# board.net
KiCad netlist of a schematic drawn in EAGLE
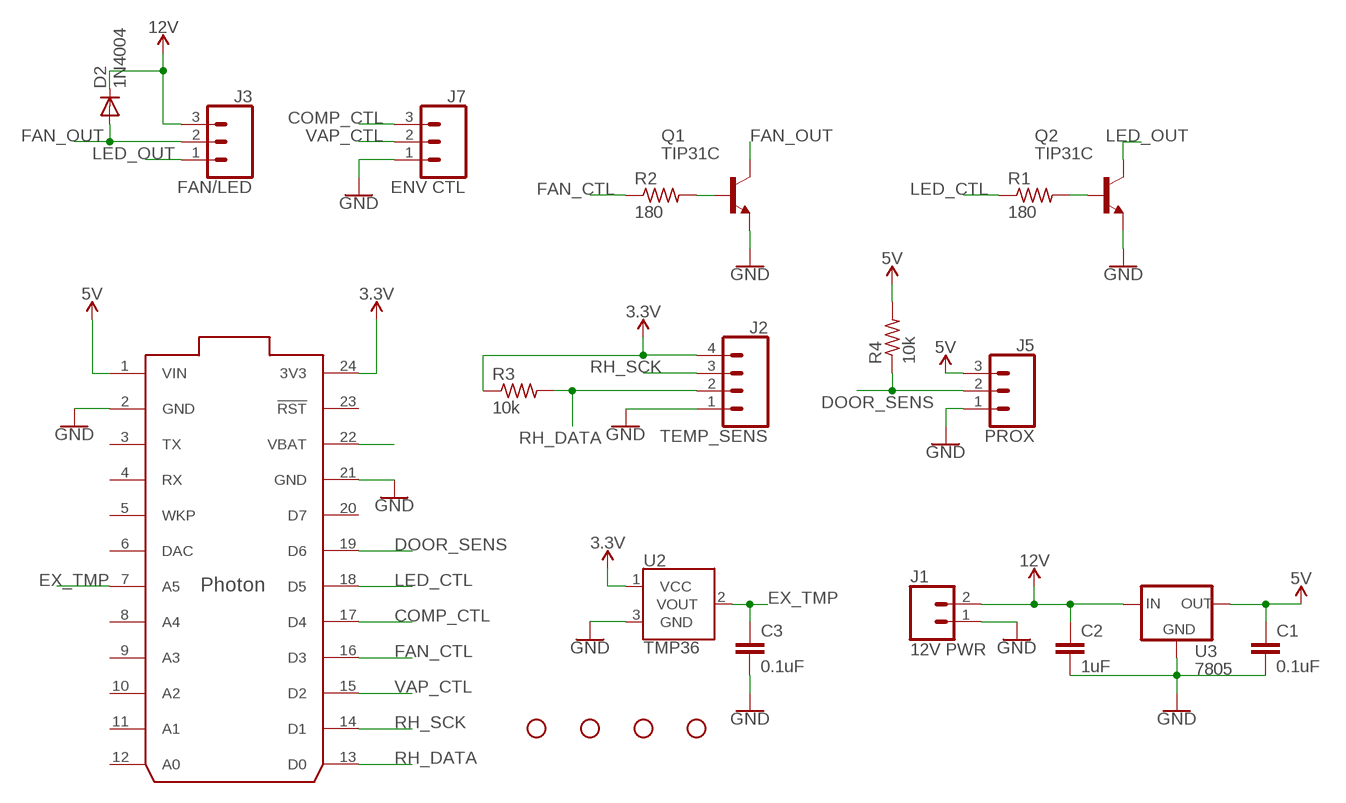
[diagram p0: schematic, sheet 1]

(export (version "E")
  (design (tool "Eeschema 10.0.6"))
  (components
    (comp (ref "C1")
      (value "0.1uF")
      (footprint "eagle-import:CAP-PTH-SMALL-KIT")
      (libsource (lib "eagle-import") (part "0.1UF-KIT-EZ-50V-20%"))
    )
    (comp (ref "C2")
      (value "1uF")
      (footprint "eagle-import:CAP-PTH-SMALL-KIT")
      (libsource (lib "eagle-import") (part "0.1UF-KIT-EZ-50V-20%"))
    )
    (comp (ref "C3")
      (value "0.1uF")
      (footprint "eagle-import:CAP-PTH-SMALL-KIT")
      (libsource (lib "eagle-import") (part "0.1UF-KIT-EZ-50V-20%"))
    )
    (comp (ref "D2")
      (value "1N4004")
      (footprint "eagle-import:DO41-10")
      (libsource (lib "eagle-import") (part "1N4004"))
    )
    (comp (ref "H1")
      (value "STAND-OFF")
      (footprint "eagle-import:STAND-OFF")
      (libsource (lib "eagle-import") (part "STAND-OFF"))
    )
    (comp (ref "H2")
      (value "STAND-OFF")
      (footprint "eagle-import:STAND-OFF")
      (libsource (lib "eagle-import") (part "STAND-OFF"))
    )
    (comp (ref "H3")
      (value "STAND-OFF")
      (footprint "eagle-import:STAND-OFF")
      (libsource (lib "eagle-import") (part "STAND-OFF"))
    )
    (comp (ref "H4")
      (value "STAND-OFF")
      (footprint "eagle-import:STAND-OFF")
      (libsource (lib "eagle-import") (part "STAND-OFF"))
    )
    (comp (ref "J1")
      (value "12V PWR")
      (footprint "eagle-import:SCREWTERMINAL-3.5MM-2")
      (libsource (lib "eagle-import") (part "CONN_023.5MM"))
    )
    (comp (ref "J2")
      (value "TEMP_SENS")
      (footprint "eagle-import:SCREWTERMINAL-3.5MM-4_LOCK")
      (libsource (lib "eagle-import") (part "CONN_04SCREW_LOCK"))
    )
    (comp (ref "J3")
      (value "FAN/LED")
      (footprint "eagle-import:SCREWTERMINAL-5MM-3")
      (libsource (lib "eagle-import") (part "CONN_03-SCREW-5MM"))
    )
    (comp (ref "J5")
      (value "PROX")
      (footprint "eagle-import:SCREWTERMINAL-5MM-3")
      (libsource (lib "eagle-import") (part "CONN_03-SCREW-5MM"))
    )
    (comp (ref "J7")
      (value "ENV CTL")
      (footprint "eagle-import:SCREWTERMINAL-5MM-3")
      (libsource (lib "eagle-import") (part "CONN_03-SCREW-5MM"))
    )
    (comp (ref "Q1")
      (value "TIP31C")
      (footprint "eagle-import:TO220")
      (libsource (lib "eagle-import") (part "TIP31C"))
    )
    (comp (ref "Q2")
      (value "TIP31C")
      (footprint "eagle-import:TO220")
      (libsource (lib "eagle-import") (part "TIP31C"))
    )
    (comp (ref "R1")
      (value "180")
      (footprint "eagle-import:0207_10")
      (libsource (lib "eagle-import") (part "R-US_0207/10"))
    )
    (comp (ref "R2")
      (value "180")
      (footprint "eagle-import:0207_10")
      (libsource (lib "eagle-import") (part "R-US_0207/10"))
    )
    (comp (ref "R3")
      (value "10k")
      (footprint "eagle-import:0207_10")
      (libsource (lib "eagle-import") (part "R-US_0207/10"))
    )
    (comp (ref "R4")
      (value "10k")
      (footprint "eagle-import:0207_10")
      (libsource (lib "eagle-import") (part "R-US_0207/10"))
    )
    (comp (ref "U$1")
      (value "PHOTON_SMD")
      (footprint "eagle-import:PHOTON_SMD")
      (libsource (lib "eagle-import") (part "PHOTON_SMD"))
    )
    (comp (ref "U2")
      (value "TMP36")
      (footprint "eagle-import:TO-92")
      (libsource (lib "eagle-import") (part "TMP36GT9"))
    )
    (comp (ref "U3")
      (value "7805")
      (footprint "eagle-import:TO-220-ALT")
      (libsource (lib "eagle-import") (part "V_REG_78XX-TO-220"))
    )
  )
  (nets
    (net (code "1") (name "/COMP_CTL") (class "Default")
      (node (ref "J7") (pin "3") (pinfunction "3_3") (pintype "passive"))
      (node (ref "U$1") (pin "17") (pinfunction "D4_17") (pintype "bidirectional"))
    )
    (net (code "2") (name "/DOOR_SENS") (class "Default")
      (node (ref "J5") (pin "2") (pinfunction "2_2") (pintype "passive"))
      (node (ref "R4") (pin "1") (pinfunction "1_1") (pintype "passive"))
      (node (ref "U$1") (pin "19") (pinfunction "D6_19") (pintype "bidirectional"))
    )
    (net (code "3") (name "/EX_TMP") (class "Default")
      (node (ref "C3") (pin "1") (pinfunction "1_1") (pintype "passive"))
      (node (ref "U$1") (pin "7") (pinfunction "A5_7") (pintype "bidirectional"))
      (node (ref "U2") (pin "2") (pinfunction "VOUT_2") (pintype "bidirectional"))
    )
    (net (code "4") (name "/FAN_CTL") (class "Default")
      (node (ref "R2") (pin "1") (pinfunction "1_1") (pintype "passive"))
      (node (ref "U$1") (pin "16") (pinfunction "D3_16") (pintype "bidirectional"))
    )
    (net (code "5") (name "/FAN_OUT") (class "Default")
      (node (ref "D2") (pin "A") (pinfunction "A_A") (pintype "passive"))
      (node (ref "J3") (pin "2") (pinfunction "2_2") (pintype "passive"))
      (node (ref "Q1") (pin "2") (pinfunction "C_2") (pintype "passive"))
    )
    (net (code "6") (name "/LED_CTL") (class "Default")
      (node (ref "R1") (pin "1") (pinfunction "1_1") (pintype "passive"))
      (node (ref "U$1") (pin "18") (pinfunction "D5_18") (pintype "bidirectional"))
    )
    (net (code "7") (name "/LED_OUT") (class "Default")
      (node (ref "J3") (pin "1") (pinfunction "1_1") (pintype "passive"))
      (node (ref "Q2") (pin "2") (pinfunction "C_2") (pintype "passive"))
    )
    (net (code "8") (name "/RH_DATA") (class "Default")
      (node (ref "J2") (pin "2") (pinfunction "2_2") (pintype "passive"))
      (node (ref "R3") (pin "2") (pinfunction "2_2") (pintype "passive"))
      (node (ref "U$1") (pin "13") (pinfunction "D0_13") (pintype "bidirectional"))
    )
    (net (code "9") (name "/RH_SCK") (class "Default")
      (node (ref "J2") (pin "3") (pinfunction "3_3") (pintype "passive"))
      (node (ref "U$1") (pin "14") (pinfunction "D1_14") (pintype "bidirectional"))
    )
    (net (code "10") (name "/VAP_CTL") (class "Default")
      (node (ref "J7") (pin "2") (pinfunction "2_2") (pintype "passive"))
      (node (ref "U$1") (pin "15") (pinfunction "D2_15") (pintype "bidirectional"))
    )
    (net (code "11") (name "3.3V") (class "Default")
      (node (ref "J2") (pin "4") (pinfunction "4_4") (pintype "passive"))
      (node (ref "R3") (pin "1") (pinfunction "1_1") (pintype "passive"))
      (node (ref "U$1") (pin "24") (pinfunction "3V3_24") (pintype "power_in"))
      (node (ref "U2") (pin "1") (pinfunction "VCC_1") (pintype "bidirectional"))
    )
    (net (code "12") (name "5V") (class "Default")
      (node (ref "C1") (pin "1") (pinfunction "1_1") (pintype "passive"))
      (node (ref "J5") (pin "3") (pinfunction "3_3") (pintype "passive"))
      (node (ref "R4") (pin "2") (pinfunction "2_2") (pintype "passive"))
      (node (ref "U$1") (pin "1") (pinfunction "VIN_1") (pintype "power_in"))
      (node (ref "U3") (pin "OUT") (pinfunction "OUT_OUT") (pintype "passive"))
    )
    (net (code "13") (name "12V") (class "Default")
      (node (ref "C2") (pin "1") (pinfunction "1_1") (pintype "passive"))
      (node (ref "D2") (pin "C") (pinfunction "C_C") (pintype "passive"))
      (node (ref "J1") (pin "2") (pinfunction "2_2") (pintype "passive"))
      (node (ref "J3") (pin "3") (pinfunction "3_3") (pintype "passive"))
      (node (ref "U3") (pin "IN") (pinfunction "IN_IN") (pintype "input"))
    )
    (net (code "14") (name "GND") (class "Default")
      (node (ref "C1") (pin "2") (pinfunction "2_2") (pintype "passive"))
      (node (ref "C2") (pin "2") (pinfunction "2_2") (pintype "passive"))
      (node (ref "C3") (pin "2") (pinfunction "2_2") (pintype "passive"))
      (node (ref "J1") (pin "1") (pinfunction "1_1") (pintype "passive"))
      (node (ref "J2") (pin "1") (pinfunction "1_1") (pintype "passive"))
      (node (ref "J5") (pin "1") (pinfunction "1_1") (pintype "passive"))
      (node (ref "J7") (pin "1") (pinfunction "1_1") (pintype "passive"))
      (node (ref "Q1") (pin "3") (pinfunction "E_3") (pintype "passive"))
      (node (ref "Q2") (pin "3") (pinfunction "E_3") (pintype "passive"))
      (node (ref "U$1") (pin "2") (pinfunction "GND_2") (pintype "power_in"))
      (node (ref "U$1") (pin "21") (pinfunction "GND_21") (pintype "power_in"))
      (node (ref "U2") (pin "3") (pinfunction "GND_3") (pintype "bidirectional"))
      (node (ref "U3") (pin "GND") (pinfunction "GND_GND") (pintype "input"))
    )
    (net (code "15") (name "Net-(Q1-B)") (class "Default")
      (node (ref "Q1") (pin "1") (pinfunction "B_1") (pintype "passive"))
      (node (ref "R2") (pin "2") (pinfunction "2_2") (pintype "passive"))
    )
    (net (code "16") (name "Net-(Q2-B)") (class "Default")
      (node (ref "Q2") (pin "1") (pinfunction "B_1") (pintype "passive"))
      (node (ref "R1") (pin "2") (pinfunction "2_2") (pintype "passive"))
    )
    (net (code "17") (name "unconnected-(U$1A-A0-Pad12)") (class "Default")
      (node (ref "U$1") (pin "12") (pinfunction "A0_12") (pintype "bidirectional"))
    )
    (net (code "18") (name "unconnected-(U$1A-A1-Pad11)") (class "Default")
      (node (ref "U$1") (pin "11") (pinfunction "A1_11") (pintype "bidirectional"))
    )
    (net (code "19") (name "unconnected-(U$1A-A2-Pad10)") (class "Default")
      (node (ref "U$1") (pin "10") (pinfunction "A2_10") (pintype "bidirectional"))
    )
    (net (code "20") (name "unconnected-(U$1A-A3-Pad9)") (class "Default")
      (node (ref "U$1") (pin "9") (pinfunction "A3_9") (pintype "bidirectional"))
    )
    (net (code "21") (name "unconnected-(U$1A-A4-Pad8)") (class "Default")
      (node (ref "U$1") (pin "8") (pinfunction "A4_8") (pintype "bidirectional"))
    )
    (net (code "22") (name "unconnected-(U$1A-D7-Pad20)") (class "Default")
      (node (ref "U$1") (pin "20") (pinfunction "D7_20") (pintype "bidirectional"))
    )
    (net (code "23") (name "unconnected-(U$1A-DAC-Pad6)") (class "Default")
      (node (ref "U$1") (pin "6") (pinfunction "DAC_6") (pintype "bidirectional"))
    )
    (net (code "24") (name "unconnected-(U$1A-RX-Pad4)") (class "Default")
      (node (ref "U$1") (pin "4") (pinfunction "RX_4") (pintype "bidirectional"))
    )
    (net (code "25") (name "unconnected-(U$1A-TX-Pad3)") (class "Default")
      (node (ref "U$1") (pin "3") (pinfunction "TX_3") (pintype "bidirectional"))
    )
    (net (code "26") (name "unconnected-(U$1A-VBAT-Pad22)") (class "Default")
      (node (ref "U$1") (pin "22") (pinfunction "VBAT_22") (pintype "power_in"))
    )
    (net (code "27") (name "unconnected-(U$1A-WKP-Pad5)") (class "Default")
      (node (ref "U$1") (pin "5") (pinfunction "WKP_5") (pintype "bidirectional"))
    )
    (net (code "28") (name "unconnected-(U$1A-~{RST}-Pad23)") (class "Default")
      (node (ref "U$1") (pin "23") (pinfunction "~{RST}_23") (pintype "bidirectional"))
    )
  )
)
